# 03_-_MAIN_BOARD.net
KiCad netlist of a schematic drawn in Altium Designer
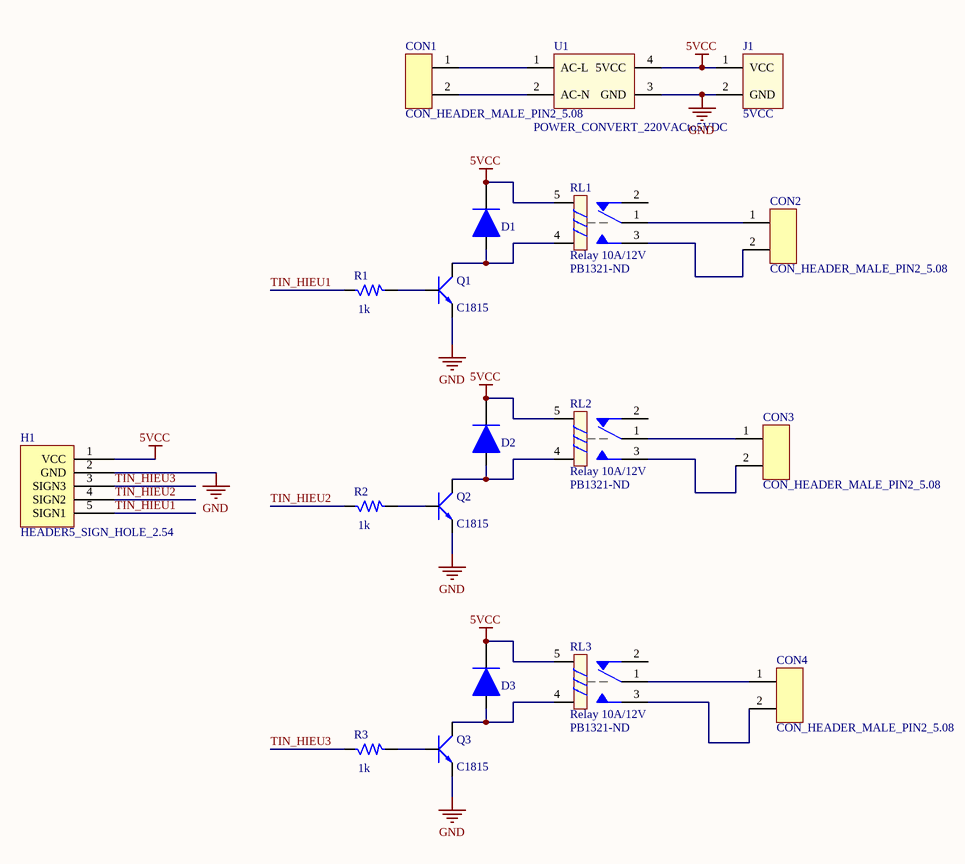
[diagram p0: [03] - MAIN BOARD.SchDoc]

(export (version "E")
  (design (tool "Eeschema 10.0.6"))
  (components
    (comp (ref "CON1")
      (value "CON_HEADER_MALE_PIN2_5.08")
      (footprint "CON_HEADER_MALE_VAC")
      (description "TERM BLOCK HDR 2POS R/A 5.08MM")
      (fields
        (field (name "MANUFACTURER") "TE Connectivity AMP Connectors")
        (field (name "MANUFACTURER PART NUMBER") "282815-2")
      )
      (libsource (lib "") (part "CON_HEADER_MALE_PIN2_5.08_1"))
    )
    (comp (ref "CON2")
      (value "CON_HEADER_MALE_PIN2_5.08")
      (footprint "CON_HEADER_MALE_PIN2")
      (description "TERM BLOCK HDR 2POS R/A 5.08MM")
      (fields
        (field (name "MANUFACTURER") "TE Connectivity AMP Connectors")
        (field (name "MANUFACTURER PART NUMBER") "282815-2")
      )
      (libsource (lib "LIB_ALTIUM") (part "CON_HEADER_MALE_PIN2_5.08"))
    )
    (comp (ref "CON3")
      (value "CON_HEADER_MALE_PIN2_5.08")
      (footprint "CON_HEADER_MALE_PIN2")
      (description "TERM BLOCK HDR 2POS R/A 5.08MM")
      (fields
        (field (name "MANUFACTURER") "TE Connectivity AMP Connectors")
        (field (name "MANUFACTURER PART NUMBER") "282815-2")
      )
      (libsource (lib "LIB_ALTIUM") (part "CON_HEADER_MALE_PIN2_5.08"))
    )
    (comp (ref "CON4")
      (value "CON_HEADER_MALE_PIN2_5.08")
      (footprint "CON_HEADER_MALE_PIN2")
      (description "TERM BLOCK HDR 2POS R/A 5.08MM")
      (fields
        (field (name "MANUFACTURER") "TE Connectivity AMP Connectors")
        (field (name "MANUFACTURER PART NUMBER") "282815-2")
      )
      (libsource (lib "LIB_ALTIUM") (part "CON_HEADER_MALE_PIN2_5.08"))
    )
    (comp (ref "D1")
      (value "DIODE_M7_taobaoSMD_1A")
      (footprint "DIODE_SMD_M7")
      (description "DIODE 1000V 1A SMD M7")
      (fields
        (field (name "MANUFACTURER") "Diodes Incorporated")
        (field (name "MANUFACTURER PART NUMBER") "1N4148W-13-F")
      )
      (libsource (lib "LIB_ALTIUM") (part "DIODE_M7_taobaoSMD_1A"))
    )
    (comp (ref "D2")
      (value "DIODE_M7_taobaoSMD_1A")
      (footprint "DIODE_SMD_M7")
      (description "DIODE 1000V 1A SMD M7")
      (fields
        (field (name "MANUFACTURER") "Diodes Incorporated")
        (field (name "MANUFACTURER PART NUMBER") "1N4148W-13-F")
      )
      (libsource (lib "LIB_ALTIUM") (part "DIODE_M7_taobaoSMD_1A"))
    )
    (comp (ref "D3")
      (value "DIODE_M7_taobaoSMD_1A")
      (footprint "DIODE_SMD_M7")
      (description "DIODE 1000V 1A SMD M7")
      (fields
        (field (name "MANUFACTURER") "Diodes Incorporated")
        (field (name "MANUFACTURER PART NUMBER") "1N4148W-13-F")
      )
      (libsource (lib "LIB_ALTIUM") (part "DIODE_M7_taobaoSMD_1A"))
    )
    (comp (ref "H1")
      (value "HEADER5_SIGN_HOLE_2.54")
      (footprint "HEADER5_SIGN_HOLE_2.54")
      (description "CONN HEADER 5 POS 2.54")
      (fields
        (field (name "MANUFACTURER") "Wurth Electronics Inc")
        (field (name "MANUFACTURER PART NUMBER") "61300511121")
      )
      (libsource (lib "LIB_ALTIUM") (part "HEADER5_SIGN_HOLE_2.54"))
    )
    (comp (ref "J1")
      (value "5VCC")
      (footprint "CON_HEADER_MALE_POWER_PIN2_FRICTIONLOCK - duplicate")
      (description "CONN HEADER VERT 2POS .100 TIN")
      (fields
        (field (name "MANUFACTURER") "TE Connectivity AMP Connectors")
        (field (name "MANUFACTURER PART NUMBER") "640456-2")
      )
      (libsource (lib "LIB_ALTIUM") (part "CON_HEADER_POWER_MALE_PIN2_2.54_1"))
    )
    (comp (ref "Q1")
      (value "C1815")
      (footprint "TRAN-NPN-SMD")
      (description "NPN 600mW, ECB")
      (fields (field (name "Comment") "TRAN-NPN-SMD"))
      (libsource (lib "LIB_ALTIUM") (part "TRAN-NPN-SMD"))
    )
    (comp (ref "Q2")
      (value "C1815")
      (footprint "TRAN-NPN-SMD")
      (description "NPN 600mW, ECB")
      (fields (field (name "Comment") "TRAN-NPN-SMD"))
      (libsource (lib "LIB_ALTIUM") (part "TRAN-NPN-SMD"))
    )
    (comp (ref "Q3")
      (value "C1815")
      (footprint "TRAN-NPN-SMD")
      (description "NPN 600mW, ECB")
      (fields (field (name "Comment") "TRAN-NPN-SMD"))
      (libsource (lib "LIB_ALTIUM") (part "TRAN-NPN-SMD"))
    )
    (comp (ref "R1")
      (value "R_1K_SMD0603_1%_1/10W")
      (footprint "RES_SMD0603")
      (description "RES SMD 1K OHM 1% 1/10W 0603")
      (fields
        (field (name "MANUFACTURER") "Yageo")
        (field (name "MANUFACTURER PART NUMBER") "RC0603FR-071KL")
        (field (name "RESISTANCE (OHMS)") "1k")
      )
      (libsource (lib "LIB_ALTIUM") (part "R_1K_SMD0603_1%_1/10W"))
    )
    (comp (ref "R2")
      (value "R_1K_SMD0603_1%_1/10W")
      (footprint "RES_SMD0603")
      (description "RES SMD 1K OHM 1% 1/10W 0603")
      (fields
        (field (name "MANUFACTURER") "Yageo")
        (field (name "MANUFACTURER PART NUMBER") "RC0603FR-071KL")
        (field (name "RESISTANCE (OHMS)") "1k")
      )
      (libsource (lib "LIB_ALTIUM") (part "R_1K_SMD0603_1%_1/10W"))
    )
    (comp (ref "R3")
      (value "R_1K_SMD0603_1%_1/10W")
      (footprint "RES_SMD0603")
      (description "RES SMD 1K OHM 1% 1/10W 0603")
      (fields
        (field (name "MANUFACTURER") "Yageo")
        (field (name "MANUFACTURER PART NUMBER") "RC0603FR-071KL")
        (field (name "RESISTANCE (OHMS)") "1k")
      )
      (libsource (lib "LIB_ALTIUM") (part "R_1K_SMD0603_1%_1/10W"))
    )
    (comp (ref "RL1")
      (value "Relay 10A/12V")
      (footprint "RELAY_HOLE5PINS_10A")
      (description "Relay SPDT,10A - 12VDC 5 Pin")
      (fields
        (field (name "MANUFACTURER") "TE Connectivity Potter & Brumfield Relays")
        (field (name "MANUFACTURER PART NUMBER") "ORWH-SH-112D,N000")
        (field (name "SUPPLIER PART NUMBER 1") "PB1321-ND")
      )
      (libsource (lib "LIB_ALTIUM") (part "RELAY_SPDT_HOLE5_10A_12VDC"))
    )
    (comp (ref "RL2")
      (value "Relay 10A/12V")
      (footprint "RELAY_HOLE5PINS_10A")
      (description "Relay SPDT,10A - 12VDC 5 Pin")
      (fields
        (field (name "MANUFACTURER") "TE Connectivity Potter & Brumfield Relays")
        (field (name "MANUFACTURER PART NUMBER") "ORWH-SH-112D,N000")
        (field (name "SUPPLIER PART NUMBER 1") "PB1321-ND")
      )
      (libsource (lib "LIB_ALTIUM") (part "RELAY_SPDT_HOLE5_10A_12VDC"))
    )
    (comp (ref "RL3")
      (value "Relay 10A/12V")
      (footprint "RELAY_HOLE5PINS_10A")
      (description "Relay SPDT,10A - 12VDC 5 Pin")
      (fields
        (field (name "MANUFACTURER") "TE Connectivity Potter & Brumfield Relays")
        (field (name "MANUFACTURER PART NUMBER") "ORWH-SH-112D,N000")
        (field (name "SUPPLIER PART NUMBER 1") "PB1321-ND")
      )
      (libsource (lib "LIB_ALTIUM") (part "RELAY_SPDT_HOLE5_10A_12VDC"))
    )
    (comp (ref "U1")
      (value "POWER_CONVERT_220VACto5VDC")
      (footprint "POWER_CONVERT220VACto5VDC")
      (libsource (lib "LIB_ALTIUM") (part "POWER_CONVERT_220VACto5VDC"))
    )
  )
  (nets
    (net (code "1") (name "/TIN_HIEU1") (class "Default")
      (node (ref "H1") (pin "5") (pinfunction "SIGN1_5") (pintype "passive"))
      (node (ref "R1") (pin "1") (pinfunction "1_1") (pintype "passive"))
    )
    (net (code "2") (name "/TIN_HIEU2") (class "Default")
      (node (ref "H1") (pin "4") (pinfunction "SIGN2_4") (pintype "passive"))
      (node (ref "R2") (pin "1") (pinfunction "1_1") (pintype "passive"))
    )
    (net (code "3") (name "/TIN_HIEU3") (class "Default")
      (node (ref "H1") (pin "3") (pinfunction "SIGN3_3") (pintype "passive"))
      (node (ref "R3") (pin "1") (pinfunction "1_1") (pintype "passive"))
    )
    (net (code "4") (name "5VCC") (class "Default")
      (node (ref "D1") (pin "K") (pinfunction "1_K") (pintype "passive"))
      (node (ref "D2") (pin "K") (pinfunction "1_K") (pintype "passive"))
      (node (ref "D3") (pin "K") (pinfunction "1_K") (pintype "passive"))
      (node (ref "H1") (pin "1") (pinfunction "VCC_1") (pintype "passive"))
      (node (ref "J1") (pin "1") (pinfunction "VCC_1") (pintype "passive"))
      (node (ref "RL1") (pin "5") (pinfunction "5_5") (pintype "passive"))
      (node (ref "RL2") (pin "5") (pinfunction "5_5") (pintype "passive"))
      (node (ref "RL3") (pin "5") (pinfunction "5_5") (pintype "passive"))
      (node (ref "U1") (pin "4") (pinfunction "5VCC_4") (pintype "passive"))
    )
    (net (code "5") (name "GND") (class "Default")
      (node (ref "H1") (pin "2") (pinfunction "GND_2") (pintype "passive"))
      (node (ref "J1") (pin "2") (pinfunction "GND_2") (pintype "passive"))
      (node (ref "Q1") (pin "2") (pinfunction "E_2") (pintype "passive"))
      (node (ref "Q2") (pin "2") (pinfunction "E_2") (pintype "passive"))
      (node (ref "Q3") (pin "2") (pinfunction "E_2") (pintype "passive"))
      (node (ref "U1") (pin "3") (pinfunction "GND_3") (pintype "passive"))
    )
    (net (code "6") (name "Net-(CON1-SIGN+)") (class "Default")
      (node (ref "CON1") (pin "1") (pinfunction "SIGN+_1") (pintype "passive"))
      (node (ref "U1") (pin "1") (pinfunction "AC-L_1") (pintype "passive"))
    )
    (net (code "7") (name "Net-(CON1-SIGN-)") (class "Default")
      (node (ref "CON1") (pin "2") (pinfunction "SIGN-_2") (pintype "passive"))
      (node (ref "U1") (pin "2") (pinfunction "AC-N_2") (pintype "passive"))
    )
    (net (code "8") (name "Net-(CON2-SIGN+)") (class "Default")
      (node (ref "CON2") (pin "1") (pinfunction "SIGN+_1") (pintype "passive"))
      (node (ref "RL1") (pin "1") (pinfunction "1_1") (pintype "passive"))
    )
    (net (code "9") (name "Net-(CON2-SIGN-)") (class "Default")
      (node (ref "CON2") (pin "2") (pinfunction "SIGN-_2") (pintype "passive"))
      (node (ref "RL1") (pin "3") (pinfunction "3_3") (pintype "passive"))
    )
    (net (code "10") (name "Net-(CON3-SIGN+)") (class "Default")
      (node (ref "CON3") (pin "1") (pinfunction "SIGN+_1") (pintype "passive"))
      (node (ref "RL2") (pin "1") (pinfunction "1_1") (pintype "passive"))
    )
    (net (code "11") (name "Net-(CON3-SIGN-)") (class "Default")
      (node (ref "CON3") (pin "2") (pinfunction "SIGN-_2") (pintype "passive"))
      (node (ref "RL2") (pin "3") (pinfunction "3_3") (pintype "passive"))
    )
    (net (code "12") (name "Net-(CON4-SIGN+)") (class "Default")
      (node (ref "CON4") (pin "1") (pinfunction "SIGN+_1") (pintype "passive"))
      (node (ref "RL3") (pin "1") (pinfunction "1_1") (pintype "passive"))
    )
    (net (code "13") (name "Net-(CON4-SIGN-)") (class "Default")
      (node (ref "CON4") (pin "2") (pinfunction "SIGN-_2") (pintype "passive"))
      (node (ref "RL3") (pin "3") (pinfunction "3_3") (pintype "passive"))
    )
    (net (code "14") (name "Net-(Q1-B)") (class "Default")
      (node (ref "Q1") (pin "1") (pinfunction "B_1") (pintype "passive"))
      (node (ref "R1") (pin "2") (pinfunction "2_2") (pintype "passive"))
    )
    (net (code "15") (name "Net-(Q1-C)") (class "Default")
      (node (ref "D1") (pin "A") (pinfunction "1_A") (pintype "passive"))
      (node (ref "Q1") (pin "3") (pinfunction "C_3") (pintype "passive"))
      (node (ref "RL1") (pin "4") (pinfunction "4_4") (pintype "passive"))
    )
    (net (code "16") (name "Net-(Q2-B)") (class "Default")
      (node (ref "Q2") (pin "1") (pinfunction "B_1") (pintype "passive"))
      (node (ref "R2") (pin "2") (pinfunction "2_2") (pintype "passive"))
    )
    (net (code "17") (name "Net-(Q2-C)") (class "Default")
      (node (ref "D2") (pin "A") (pinfunction "1_A") (pintype "passive"))
      (node (ref "Q2") (pin "3") (pinfunction "C_3") (pintype "passive"))
      (node (ref "RL2") (pin "4") (pinfunction "4_4") (pintype "passive"))
    )
    (net (code "18") (name "Net-(Q3-B)") (class "Default")
      (node (ref "Q3") (pin "1") (pinfunction "B_1") (pintype "passive"))
      (node (ref "R3") (pin "2") (pinfunction "2_2") (pintype "passive"))
    )
    (net (code "19") (name "Net-(Q3-C)") (class "Default")
      (node (ref "D3") (pin "A") (pinfunction "1_A") (pintype "passive"))
      (node (ref "Q3") (pin "3") (pinfunction "C_3") (pintype "passive"))
      (node (ref "RL3") (pin "4") (pinfunction "4_4") (pintype "passive"))
    )
    (net (code "20") (name "unconnected-(RL1-Pad2)") (class "Default")
      (node (ref "RL1") (pin "2") (pinfunction "2_2") (pintype "passive"))
    )
    (net (code "21") (name "unconnected-(RL2-Pad2)") (class "Default")
      (node (ref "RL2") (pin "2") (pinfunction "2_2") (pintype "passive"))
    )
    (net (code "22") (name "unconnected-(RL3-Pad2)") (class "Default")
      (node (ref "RL3") (pin "2") (pinfunction "2_2") (pintype "passive"))
    )
  )
)
